# hhv-dcdarknet-varient-5.net
KiCad netlist of a schematic drawn in EAGLE
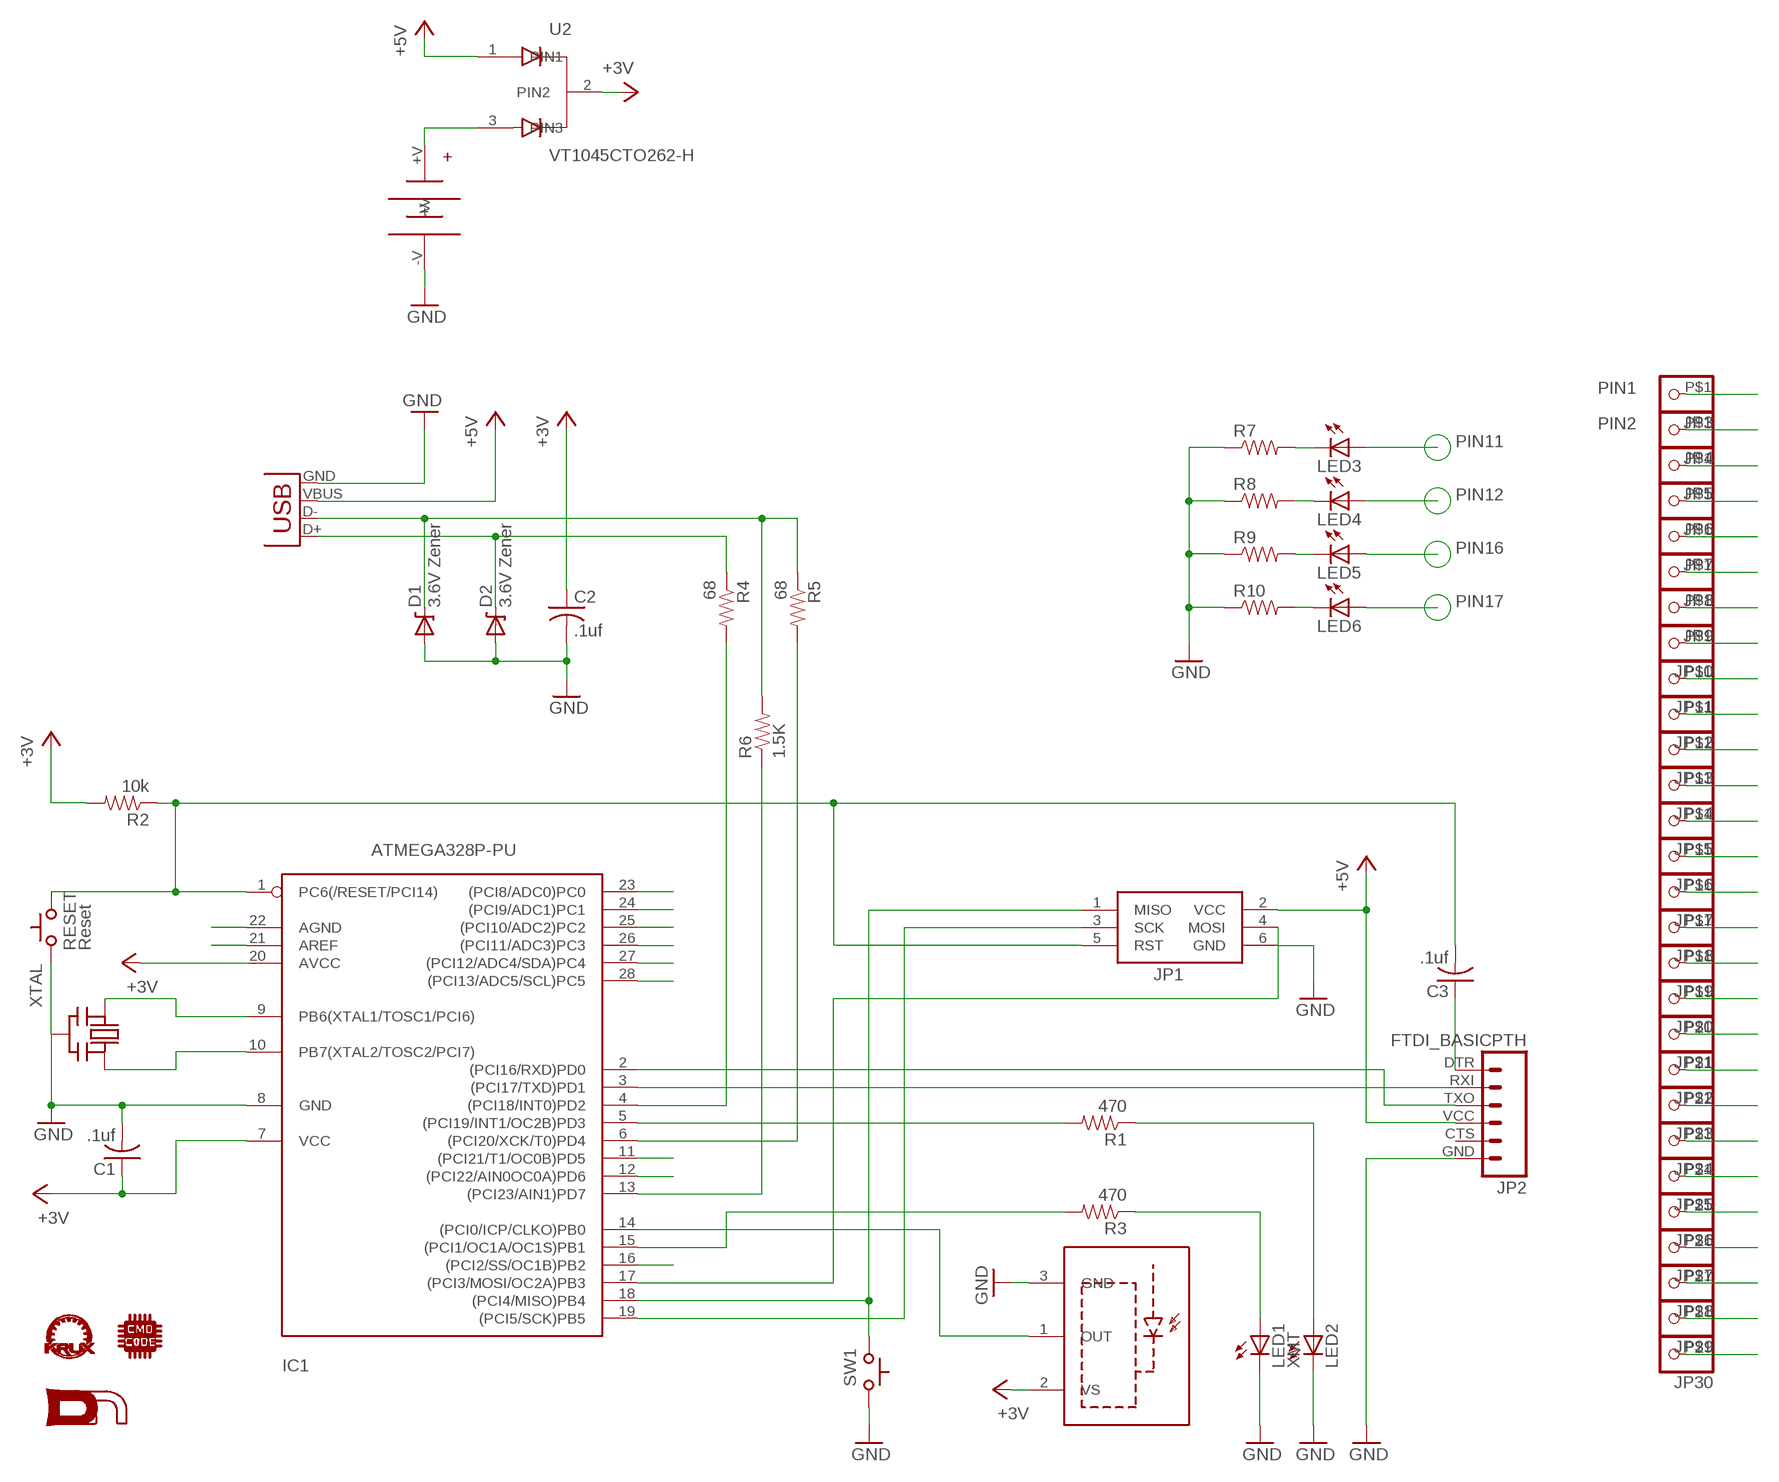
[diagram p0: schematic, sheet 1]

(export (version "E")
  (design (tool "Eeschema 10.0.6"))
  (components
    (comp (ref "C1")
      (value ".1uf")
      (footprint "eagle-import:C025-030X050")
      (libsource (lib "eagle-import") (part "C-US025-030X050"))
    )
    (comp (ref "C2")
      (value ".1uf")
      (footprint "eagle-import:C025-030X050")
      (libsource (lib "eagle-import") (part "C-US025-030X050"))
    )
    (comp (ref "C3")
      (value ".1uf")
      (footprint "eagle-import:C025-030X050")
      (libsource (lib "eagle-import") (part "C-US025-030X050"))
    )
    (comp (ref "D1")
      (value "3.6V Zener")
      (footprint "eagle-import:DIODE-ZENER")
      (libsource (lib "eagle-import") (part "DIODE-ZENERPTH"))
    )
    (comp (ref "D2")
      (value "3.6V Zener")
      (footprint "eagle-import:DIODE-ZENER")
      (libsource (lib "eagle-import") (part "DIODE-ZENERPTH"))
    )
    (comp (ref "IC1")
      (value "ATMEGA328P-PU")
      (footprint "eagle-import:DIL28-3")
      (libsource (lib "eagle-import") (part "ATMEGA168PV-10"))
    )
    (comp (ref "JP1")
      (value "JP1")
      (footprint "eagle-import:AVRISP")
      (libsource (lib "eagle-import") (part "AVRISP-6"))
    )
    (comp (ref "JP2")
      (value "FTDI_BASICPTH")
      (footprint "eagle-import:FTDI_BASIC")
      (libsource (lib "eagle-import") (part "FTDI_BASICPTH"))
    )
    (comp (ref "JP3")
      (value "PINHD-1X11X1_SQUARE")
      (footprint "eagle-import:1X1-SMALL_CUT")
      (libsource (lib "eagle-import") (part "PINHD-1X11X1_SQUARE"))
    )
    (comp (ref "JP4")
      (value "PINHD-1X11X1_SQUARE")
      (footprint "eagle-import:1X1-SMALL_CUT")
      (libsource (lib "eagle-import") (part "PINHD-1X11X1_SQUARE"))
    )
    (comp (ref "JP5")
      (value "PINHD-1X11X1_SQUARE")
      (footprint "eagle-import:1X1-SMALL_CUT")
      (libsource (lib "eagle-import") (part "PINHD-1X11X1_SQUARE"))
    )
    (comp (ref "JP6")
      (value "PINHD-1X11X1_SQUARE")
      (footprint "eagle-import:1X1-SMALL_CUT")
      (libsource (lib "eagle-import") (part "PINHD-1X11X1_SQUARE"))
    )
    (comp (ref "JP7")
      (value "PINHD-1X11X1_SQUARE")
      (footprint "eagle-import:1X1-SMALL_CUT")
      (libsource (lib "eagle-import") (part "PINHD-1X11X1_SQUARE"))
    )
    (comp (ref "JP8")
      (value "PINHD-1X11X1_SQUARE")
      (footprint "eagle-import:1X1-SMALL_CUT")
      (libsource (lib "eagle-import") (part "PINHD-1X11X1_SQUARE"))
    )
    (comp (ref "JP9")
      (value "PINHD-1X11X1_SQUARE")
      (footprint "eagle-import:1X1-SMALL_CUT")
      (libsource (lib "eagle-import") (part "PINHD-1X11X1_SQUARE"))
    )
    (comp (ref "JP10")
      (value "PINHD-1X11X1_SQUARE")
      (footprint "eagle-import:1X1-SMALL_CUT")
      (libsource (lib "eagle-import") (part "PINHD-1X11X1_SQUARE"))
    )
    (comp (ref "JP11")
      (value "PINHD-1X11X1_SQUARE")
      (footprint "eagle-import:1X1-SMALL_CUT")
      (libsource (lib "eagle-import") (part "PINHD-1X11X1_SQUARE"))
    )
    (comp (ref "JP12")
      (value "PINHD-1X11X1_SQUARE")
      (footprint "eagle-import:1X1-SMALL_CUT")
      (libsource (lib "eagle-import") (part "PINHD-1X11X1_SQUARE"))
    )
    (comp (ref "JP13")
      (value "PINHD-1X11X1_SQUARE")
      (footprint "eagle-import:1X1-SMALL_CUT")
      (libsource (lib "eagle-import") (part "PINHD-1X11X1_SQUARE"))
    )
    (comp (ref "JP14")
      (value "PINHD-1X11X1_SQUARE")
      (footprint "eagle-import:1X1-SMALL_CUT")
      (libsource (lib "eagle-import") (part "PINHD-1X11X1_SQUARE"))
    )
    (comp (ref "JP15")
      (value "PINHD-1X11X1_SQUARE")
      (footprint "eagle-import:1X1-SMALL_CUT")
      (libsource (lib "eagle-import") (part "PINHD-1X11X1_SQUARE"))
    )
    (comp (ref "JP16")
      (value "PINHD-1X11X1_SQUARE")
      (footprint "eagle-import:1X1-SMALL_CUT")
      (libsource (lib "eagle-import") (part "PINHD-1X11X1_SQUARE"))
    )
    (comp (ref "JP17")
      (value "PINHD-1X11X1_SQUARE")
      (footprint "eagle-import:1X1-SMALL_CUT")
      (libsource (lib "eagle-import") (part "PINHD-1X11X1_SQUARE"))
    )
    (comp (ref "JP18")
      (value "PINHD-1X11X1_SQUARE")
      (footprint "eagle-import:1X1-SMALL_CUT")
      (libsource (lib "eagle-import") (part "PINHD-1X11X1_SQUARE"))
    )
    (comp (ref "JP19")
      (value "PINHD-1X11X1_SQUARE")
      (footprint "eagle-import:1X1-SMALL_CUT")
      (libsource (lib "eagle-import") (part "PINHD-1X11X1_SQUARE"))
    )
    (comp (ref "JP20")
      (value "PINHD-1X11X1_SQUARE")
      (footprint "eagle-import:1X1-SMALL_CUT")
      (libsource (lib "eagle-import") (part "PINHD-1X11X1_SQUARE"))
    )
    (comp (ref "JP21")
      (value "PINHD-1X11X1_SQUARE")
      (footprint "eagle-import:1X1-SMALL_CUT")
      (libsource (lib "eagle-import") (part "PINHD-1X11X1_SQUARE"))
    )
    (comp (ref "JP22")
      (value "PINHD-1X11X1_SQUARE")
      (footprint "eagle-import:1X1-SMALL_CUT")
      (libsource (lib "eagle-import") (part "PINHD-1X11X1_SQUARE"))
    )
    (comp (ref "JP23")
      (value "PINHD-1X11X1_SQUARE")
      (footprint "eagle-import:1X1-SMALL_CUT")
      (libsource (lib "eagle-import") (part "PINHD-1X11X1_SQUARE"))
    )
    (comp (ref "JP24")
      (value "PINHD-1X11X1_SQUARE")
      (footprint "eagle-import:1X1-SMALL_CUT")
      (libsource (lib "eagle-import") (part "PINHD-1X11X1_SQUARE"))
    )
    (comp (ref "JP25")
      (value "PINHD-1X11X1_SQUARE")
      (footprint "eagle-import:1X1-SMALL_CUT")
      (libsource (lib "eagle-import") (part "PINHD-1X11X1_SQUARE"))
    )
    (comp (ref "JP26")
      (value "PINHD-1X11X1-SMALL")
      (footprint "eagle-import:1X1-SMALL")
      (libsource (lib "eagle-import") (part "PINHD-1X11X1-SMALL"))
    )
    (comp (ref "JP27")
      (value "PINHD-1X11X1-SMALL")
      (footprint "eagle-import:1X1-SMALL")
      (libsource (lib "eagle-import") (part "PINHD-1X11X1-SMALL"))
    )
    (comp (ref "JP28")
      (value "PINHD-1X11X1-SMALL")
      (footprint "eagle-import:1X1-SMALL")
      (libsource (lib "eagle-import") (part "PINHD-1X11X1-SMALL"))
    )
    (comp (ref "JP29")
      (value "PINHD-1X11X1-SMALL")
      (footprint "eagle-import:1X1-SMALL")
      (libsource (lib "eagle-import") (part "PINHD-1X11X1-SMALL"))
    )
    (comp (ref "JP30")
      (value "PINHD-1X11X1-SMALL")
      (footprint "eagle-import:1X1-SMALL")
      (libsource (lib "eagle-import") (part "PINHD-1X11X1-SMALL"))
    )
    (comp (ref "LED1")
      (value "XMT")
      (footprint "eagle-import:LED5MM-FLAT")
      (libsource (lib "eagle-import") (part "LED5MM-FLAT"))
    )
    (comp (ref "LED2")
      (value "LED5MM-FLAT")
      (footprint "eagle-import:LED5MM-FLAT")
      (libsource (lib "eagle-import") (part "LED5MM-FLAT"))
    )
    (comp (ref "LED3")
      (value "LED1206")
      (footprint "eagle-import:LED-1206")
      (libsource (lib "eagle-import") (part "SparkFun_LED1206"))
    )
    (comp (ref "LED4")
      (value "LED1206")
      (footprint "eagle-import:LED-1206")
      (libsource (lib "eagle-import") (part "SparkFun_LED1206"))
    )
    (comp (ref "LED5")
      (value "LED1206")
      (footprint "eagle-import:LED-1206")
      (libsource (lib "eagle-import") (part "SparkFun_LED1206"))
    )
    (comp (ref "LED6")
      (value "LED1206")
      (footprint "eagle-import:LED-1206")
      (libsource (lib "eagle-import") (part "SparkFun_LED1206"))
    )
    (comp (ref "R1")
      (value "470")
      (footprint "eagle-import:AXIAL-0.3")
      (libsource (lib "eagle-import") (part "RESISTORAXIAL-0.3"))
    )
    (comp (ref "R2")
      (value "10k")
      (footprint "eagle-import:AXIAL-0.3")
      (libsource (lib "eagle-import") (part "RESISTORAXIAL-0.3"))
    )
    (comp (ref "R3")
      (value "470")
      (footprint "eagle-import:AXIAL-0.3")
      (libsource (lib "eagle-import") (part "RESISTORAXIAL-0.3"))
    )
    (comp (ref "R4")
      (value "68")
      (footprint "eagle-import:AXIAL-0.3")
      (libsource (lib "eagle-import") (part "RESISTORAXIAL-0.3"))
    )
    (comp (ref "R5")
      (value "68")
      (footprint "eagle-import:AXIAL-0.3")
      (libsource (lib "eagle-import") (part "RESISTORAXIAL-0.3"))
    )
    (comp (ref "R6")
      (value "1.5K")
      (footprint "eagle-import:AXIAL-0.3")
      (libsource (lib "eagle-import") (part "RESISTORAXIAL-0.3"))
    )
    (comp (ref "R7")
      (value "RESISTOR1206")
      (footprint "eagle-import:1206")
      (libsource (lib "eagle-import") (part "SparkFun_RESISTOR1206"))
    )
    (comp (ref "R8")
      (value "RESISTOR1206")
      (footprint "eagle-import:1206")
      (libsource (lib "eagle-import") (part "SparkFun_RESISTOR1206"))
    )
    (comp (ref "R9")
      (value "RESISTOR1206")
      (footprint "eagle-import:1206")
      (libsource (lib "eagle-import") (part "SparkFun_RESISTOR1206"))
    )
    (comp (ref "R10")
      (value "RESISTOR1206")
      (footprint "eagle-import:1206")
      (libsource (lib "eagle-import") (part "SparkFun_RESISTOR1206"))
    )
    (comp (ref "RESET")
      (value "Reset")
      (footprint "eagle-import:TACTILE-2PIN")
      (libsource (lib "eagle-import") (part "SWITCH_TACTILETACTILE-2PIN"))
    )
    (comp (ref "SW1")
      (value "SWITCH_TACTILETACTILE-2PIN")
      (footprint "eagle-import:TACTILE-2PIN")
      (libsource (lib "eagle-import") (part "SWITCH_TACTILETACTILE-2PIN"))
    )
    (comp (ref "U$1")
      (value "DN_LOGO")
      (footprint "eagle-import:DN_LOGO")
      (libsource (lib "eagle-import") (part "DN_LOGO"))
    )
    (comp (ref "U$2")
      (value "CMDC0DE_LOGO")
      (footprint "eagle-import:CMDC0DE")
      (libsource (lib "eagle-import") (part "CMDC0DE_LOGO"))
    )
    (comp (ref "U$3")
      (value "KRUX_LOGO")
      (footprint "eagle-import:KRUX_LOGO")
      (libsource (lib "eagle-import") (part "KRUX_LOGO"))
    )
    (comp (ref "U$5")
      (value "12BH423-GR3-CELL_NOBORDER")
      (footprint "eagle-import:3-AAA-CELL_NOBORDER")
      (libsource (lib "eagle-import") (part "12BH423-GR3-CELL_NOBORDER"))
    )
    (comp (ref "U1")
      (value "RCV")
      (footprint "eagle-import:IR-MODULE")
      (libsource (lib "eagle-import") (part "SOP22"))
    )
    (comp (ref "U2")
      (value "VT1045CTO262-H")
      (footprint "eagle-import:TO262-H")
      (libsource (lib "eagle-import") (part "VT1045CTO262-H"))
    )
    (comp (ref "X2")
      (value "USB")
      (footprint "eagle-import:USB-B-PTH")
      (libsource (lib "eagle-import") (part "USBPTH"))
    )
    (comp (ref "XTAL")
      (value "CERMOSCILL-THM")
      (footprint "eagle-import:CERM_OSC")
      (libsource (lib "eagle-import") (part "CERMOSCILL-THM"))
    )
  )
  (nets
    (net (code "1") (name "+3V") (class "Default")
      (node (ref "C1") (pin "1") (pinfunction "1_1") (pintype "passive"))
      (node (ref "C2") (pin "1") (pinfunction "1_1") (pintype "passive"))
      (node (ref "IC1") (pin "20") (pinfunction "AVCC_20") (pintype "bidirectional"))
      (node (ref "IC1") (pin "7") (pinfunction "VCC_7") (pintype "bidirectional"))
      (node (ref "JP22") (pin "P$1") (pinfunction "1_P$1") (pintype "passive"))
      (node (ref "JP9") (pin "P$1") (pinfunction "1_P$1") (pintype "passive"))
      (node (ref "R2") (pin "P$2") (pinfunction "2_P$2") (pintype "passive"))
      (node (ref "U1") (pin "2") (pinfunction "VS_2") (pintype "bidirectional"))
      (node (ref "U2") (pin "2") (pinfunction "PIN2_2") (pintype "bidirectional"))
    )
    (net (code "2") (name "+5V") (class "Default")
      (node (ref "JP1") (pin "2") (pinfunction "VCC_2") (pintype "power_in"))
      (node (ref "JP2") (pin "VCC") (pinfunction "4_VCC") (pintype "passive"))
      (node (ref "U2") (pin "1") (pinfunction "PIN1_1") (pintype "bidirectional"))
      (node (ref "X2") (pin "VBUS") (pinfunction "VBUS_VBUS") (pintype "bidirectional"))
    )
    (net (code "3") (name "/PIN1") (class "Default")
      (node (ref "C3") (pin "2") (pinfunction "2_2") (pintype "passive"))
      (node (ref "IC1") (pin "1") (pinfunction "PC6(/RESET/PCI14)_1") (pintype "bidirectional"))
      (node (ref "JP1") (pin "5") (pinfunction "RST_5") (pintype "output"))
      (node (ref "JP3") (pin "P$1") (pinfunction "1_P$1") (pintype "passive"))
      (node (ref "R2") (pin "P$1") (pinfunction "1_P$1") (pintype "passive"))
      (node (ref "RESET") (pin "P$1") (pinfunction "A_P$1") (pintype "passive"))
    )
    (net (code "4") (name "/PIN2") (class "Default")
      (node (ref "IC1") (pin "2") (pinfunction "(PCI16/RXD)PD0_2") (pintype "bidirectional"))
      (node (ref "JP2") (pin "TXO") (pinfunction "3_TXO") (pintype "passive"))
      (node (ref "JP4") (pin "P$1") (pinfunction "1_P$1") (pintype "passive"))
    )
    (net (code "5") (name "/PIN3") (class "Default")
      (node (ref "IC1") (pin "3") (pinfunction "(PCI17/TXD)PD1_3") (pintype "bidirectional"))
      (node (ref "JP2") (pin "RXI") (pinfunction "2_RXI") (pintype "passive"))
      (node (ref "JP5") (pin "P$1") (pinfunction "1_P$1") (pintype "passive"))
    )
    (net (code "6") (name "/PIN4") (class "Default")
      (node (ref "IC1") (pin "4") (pinfunction "(PCI18/INT0)PD2_4") (pintype "bidirectional"))
      (node (ref "JP6") (pin "P$1") (pinfunction "1_P$1") (pintype "passive"))
      (node (ref "R4") (pin "P$2") (pinfunction "2_P$2") (pintype "passive"))
    )
    (net (code "7") (name "/PIN5") (class "Default")
      (node (ref "IC1") (pin "5") (pinfunction "(PCI19/INT1/OC2B)PD3_5") (pintype "bidirectional"))
      (node (ref "JP7") (pin "P$1") (pinfunction "1_P$1") (pintype "passive"))
      (node (ref "R1") (pin "P$2") (pinfunction "2_P$2") (pintype "passive"))
    )
    (net (code "8") (name "/PIN6") (class "Default")
      (node (ref "IC1") (pin "6") (pinfunction "(PCI20/XCK/T0)PD4_6") (pintype "bidirectional"))
      (node (ref "JP8") (pin "P$1") (pinfunction "1_P$1") (pintype "passive"))
      (node (ref "R5") (pin "P$2") (pinfunction "2_P$2") (pintype "passive"))
    )
    (net (code "9") (name "/PIN9") (class "Default")
      (node (ref "IC1") (pin "9") (pinfunction "PB6(XTAL1/TOSC1/PCI6)_9") (pintype "bidirectional"))
      (node (ref "JP11") (pin "P$1") (pinfunction "1_P$1") (pintype "passive"))
      (node (ref "XTAL") (pin "P$1") (pinfunction "IN_P$1") (pintype "bidirectional"))
    )
    (net (code "10") (name "/PIN10") (class "Default")
      (node (ref "IC1") (pin "10") (pinfunction "PB7(XTAL2/TOSC2/PCI7)_10") (pintype "bidirectional"))
      (node (ref "JP12") (pin "P$1") (pinfunction "1_P$1") (pintype "passive"))
      (node (ref "XTAL") (pin "P$3") (pinfunction "OUT_P$3") (pintype "bidirectional"))
    )
    (net (code "11") (name "/PIN11") (class "Default")
      (node (ref "IC1") (pin "11") (pinfunction "(PCI21/T1/OC0B)PD5_11") (pintype "bidirectional"))
      (node (ref "JP13") (pin "P$1") (pinfunction "1_P$1") (pintype "passive"))
      (node (ref "LED3") (pin "A") (pinfunction "A_A") (pintype "passive"))
    )
    (net (code "12") (name "/PIN12") (class "Default")
      (node (ref "IC1") (pin "12") (pinfunction "(PCI22/AIN0OC0A)PD6_12") (pintype "bidirectional"))
      (node (ref "JP14") (pin "P$1") (pinfunction "1_P$1") (pintype "passive"))
      (node (ref "LED4") (pin "A") (pinfunction "A_A") (pintype "passive"))
    )
    (net (code "13") (name "/PIN13") (class "Default")
      (node (ref "IC1") (pin "13") (pinfunction "(PCI23/AIN1)PD7_13") (pintype "bidirectional"))
      (node (ref "JP15") (pin "P$1") (pinfunction "1_P$1") (pintype "passive"))
      (node (ref "R6") (pin "P$1") (pinfunction "1_P$1") (pintype "passive"))
    )
    (net (code "14") (name "/PIN14") (class "Default")
      (node (ref "IC1") (pin "14") (pinfunction "(PCI0/ICP/CLKO)PB0_14") (pintype "bidirectional"))
      (node (ref "JP16") (pin "P$1") (pinfunction "1_P$1") (pintype "passive"))
      (node (ref "U1") (pin "1") (pinfunction "OUT_1") (pintype "bidirectional"))
    )
    (net (code "15") (name "/PIN15") (class "Default")
      (node (ref "IC1") (pin "15") (pinfunction "(PCI1/OC1A/OC1S)PB1_15") (pintype "bidirectional"))
      (node (ref "JP17") (pin "P$1") (pinfunction "1_P$1") (pintype "passive"))
      (node (ref "R3") (pin "P$2") (pinfunction "2_P$2") (pintype "passive"))
    )
    (net (code "16") (name "/PIN16") (class "Default")
      (node (ref "IC1") (pin "16") (pinfunction "(PCI2/SS/OC1B)PB2_16") (pintype "bidirectional"))
      (node (ref "JP18") (pin "P$1") (pinfunction "1_P$1") (pintype "passive"))
      (node (ref "LED5") (pin "A") (pinfunction "A_A") (pintype "passive"))
    )
    (net (code "17") (name "/PIN17") (class "Default")
      (node (ref "IC1") (pin "17") (pinfunction "(PCI3/MOSI/OC2A)PB3_17") (pintype "bidirectional"))
      (node (ref "JP1") (pin "4") (pinfunction "MOSI_4") (pintype "output"))
      (node (ref "JP19") (pin "P$1") (pinfunction "1_P$1") (pintype "passive"))
      (node (ref "LED6") (pin "A") (pinfunction "A_A") (pintype "passive"))
    )
    (net (code "18") (name "/PIN18") (class "Default")
      (node (ref "IC1") (pin "18") (pinfunction "(PCI4/MISO)PB4_18") (pintype "bidirectional"))
      (node (ref "JP1") (pin "1") (pinfunction "MISO_1") (pintype "input"))
      (node (ref "JP20") (pin "P$1") (pinfunction "1_P$1") (pintype "passive"))
      (node (ref "SW1") (pin "P$2") (pinfunction "C_P$2") (pintype "passive"))
    )
    (net (code "19") (name "/PIN19") (class "Default")
      (node (ref "IC1") (pin "19") (pinfunction "(PCI5/SCK)PB5_19") (pintype "bidirectional"))
      (node (ref "JP1") (pin "3") (pinfunction "SCK_3") (pintype "output"))
      (node (ref "JP21") (pin "P$1") (pinfunction "1_P$1") (pintype "passive"))
    )
    (net (code "20") (name "/PIN21") (class "Default")
      (node (ref "IC1") (pin "21") (pinfunction "AREF_21") (pintype "bidirectional"))
      (node (ref "JP23") (pin "P$1") (pinfunction "1_P$1") (pintype "passive"))
    )
    (net (code "21") (name "/PIN22") (class "Default")
      (node (ref "IC1") (pin "22") (pinfunction "AGND_22") (pintype "bidirectional"))
      (node (ref "JP24") (pin "P$1") (pinfunction "1_P$1") (pintype "passive"))
    )
    (net (code "22") (name "/PIN23") (class "Default")
      (node (ref "IC1") (pin "23") (pinfunction "(PCI8/ADC0)PC0_23") (pintype "bidirectional"))
      (node (ref "JP25") (pin "P$1") (pinfunction "1_P$1") (pintype "passive"))
    )
    (net (code "23") (name "/PIN24") (class "Default")
      (node (ref "IC1") (pin "24") (pinfunction "(PCI9/ADC1)PC1_24") (pintype "bidirectional"))
      (node (ref "JP26") (pin "P$1") (pinfunction "1_P$1") (pintype "passive"))
    )
    (net (code "24") (name "/PIN25") (class "Default")
      (node (ref "IC1") (pin "25") (pinfunction "(PCI10/ADC2)PC2_25") (pintype "bidirectional"))
      (node (ref "JP27") (pin "P$1") (pinfunction "1_P$1") (pintype "passive"))
    )
    (net (code "25") (name "/PIN26") (class "Default")
      (node (ref "IC1") (pin "26") (pinfunction "(PCI11/ADC3)PC3_26") (pintype "bidirectional"))
      (node (ref "JP28") (pin "P$1") (pinfunction "1_P$1") (pintype "passive"))
    )
    (net (code "26") (name "/PIN27") (class "Default")
      (node (ref "IC1") (pin "27") (pinfunction "(PCI12/ADC4/SDA)PC4_27") (pintype "bidirectional"))
      (node (ref "JP29") (pin "P$1") (pinfunction "1_P$1") (pintype "passive"))
    )
    (net (code "27") (name "/PIN28") (class "Default")
      (node (ref "IC1") (pin "28") (pinfunction "(PCI13/ADC5/SCL)PC5_28") (pintype "bidirectional"))
      (node (ref "JP30") (pin "P$1") (pinfunction "1_P$1") (pintype "passive"))
    )
    (net (code "28") (name "GND") (class "Default")
      (node (ref "C1") (pin "2") (pinfunction "2_2") (pintype "passive"))
      (node (ref "C2") (pin "2") (pinfunction "2_2") (pintype "passive"))
      (node (ref "D1") (pin "P$2") (pinfunction "A_P$2") (pintype "passive"))
      (node (ref "D2") (pin "P$2") (pinfunction "A_P$2") (pintype "passive"))
      (node (ref "IC1") (pin "8") (pinfunction "GND_8") (pintype "bidirectional"))
      (node (ref "JP1") (pin "6") (pinfunction "GND_6") (pintype "power_in"))
      (node (ref "JP10") (pin "P$1") (pinfunction "1_P$1") (pintype "passive"))
      (node (ref "JP2") (pin "GND") (pinfunction "6_GND") (pintype "passive"))
      (node (ref "LED1") (pin "K") (pinfunction "C_K") (pintype "passive"))
      (node (ref "LED2") (pin "K") (pinfunction "C_K") (pintype "passive"))
      (node (ref "R10") (pin "1") (pinfunction "1_1") (pintype "passive"))
      (node (ref "R7") (pin "1") (pinfunction "1_1") (pintype "passive"))
      (node (ref "R8") (pin "1") (pinfunction "1_1") (pintype "passive"))
      (node (ref "R9") (pin "1") (pinfunction "1_1") (pintype "passive"))
      (node (ref "RESET") (pin "P$2") (pinfunction "C_P$2") (pintype "passive"))
      (node (ref "SW1") (pin "P$1") (pinfunction "A_P$1") (pintype "passive"))
      (node (ref "U$5") (pin "-V") (pinfunction "-V_-V") (pintype "bidirectional"))
      (node (ref "U1") (pin "3") (pinfunction "GND_3") (pintype "bidirectional"))
      (node (ref "X2") (pin "GND") (pinfunction "GND_GND") (pintype "bidirectional"))
      (node (ref "XTAL") (pin "P$2") (pinfunction "GND_P$2") (pintype "bidirectional"))
    )
    (net (code "29") (name "Net-(D1-C)") (class "Default")
      (node (ref "D1") (pin "P$1") (pinfunction "C_P$1") (pintype "passive"))
      (node (ref "R5") (pin "P$1") (pinfunction "1_P$1") (pintype "passive"))
      (node (ref "R6") (pin "P$2") (pinfunction "2_P$2") (pintype "passive"))
      (node (ref "X2") (pin "D-") (pinfunction "D-_D-") (pintype "bidirectional"))
    )
    (net (code "30") (name "Net-(D2-C)") (class "Default")
      (node (ref "D2") (pin "P$1") (pinfunction "C_P$1") (pintype "passive"))
      (node (ref "R4") (pin "P$1") (pinfunction "1_P$1") (pintype "passive"))
      (node (ref "X2") (pin "D+") (pinfunction "D+_D+") (pintype "bidirectional"))
    )
    (net (code "31") (name "Net-(JP2-1)") (class "Default")
      (node (ref "C3") (pin "1") (pinfunction "1_1") (pintype "passive"))
      (node (ref "JP2") (pin "DTR") (pinfunction "1_DTR") (pintype "passive"))
    )
    (net (code "32") (name "Net-(LED3-PadC)") (class "Default")
      (node (ref "LED3") (pin "C") (pinfunction "C_C") (pintype "passive"))
      (node (ref "R7") (pin "2") (pinfunction "2_2") (pintype "passive"))
    )
    (net (code "33") (name "Net-(LED4-PadC)") (class "Default")
      (node (ref "LED4") (pin "C") (pinfunction "C_C") (pintype "passive"))
      (node (ref "R8") (pin "2") (pinfunction "2_2") (pintype "passive"))
    )
    (net (code "34") (name "Net-(LED5-PadC)") (class "Default")
      (node (ref "LED5") (pin "C") (pinfunction "C_C") (pintype "passive"))
      (node (ref "R9") (pin "2") (pinfunction "2_2") (pintype "passive"))
    )
    (net (code "35") (name "Net-(LED6-PadC)") (class "Default")
      (node (ref "LED6") (pin "C") (pinfunction "C_C") (pintype "passive"))
      (node (ref "R10") (pin "2") (pinfunction "2_2") (pintype "passive"))
    )
    (net (code "36") (name "Net-(R1-1)") (class "Default")
      (node (ref "LED2") (pin "A") (pinfunction "A_A") (pintype "passive"))
      (node (ref "R1") (pin "P$1") (pinfunction "1_P$1") (pintype "passive"))
    )
    (net (code "37") (name "Net-(R3-1)") (class "Default")
      (node (ref "LED1") (pin "A") (pinfunction "A_A") (pintype "passive"))
      (node (ref "R3") (pin "P$1") (pinfunction "1_P$1") (pintype "passive"))
    )
    (net (code "38") (name "Net-(U2-PIN3)") (class "Default")
      (node (ref "U$5") (pin "+V") (pinfunction "+V_+V") (pintype "bidirectional"))
      (node (ref "U2") (pin "3") (pinfunction "PIN3_3") (pintype "bidirectional"))
    )
    (net (code "39") (name "unconnected-(JP2-5-PadCTS)") (class "Default")
      (node (ref "JP2") (pin "CTS") (pinfunction "5_CTS") (pintype "passive"))
    )
  )
)
